# SP_Display_Line_0603.net
KiCad netlist of a schematic drawn in EAGLE
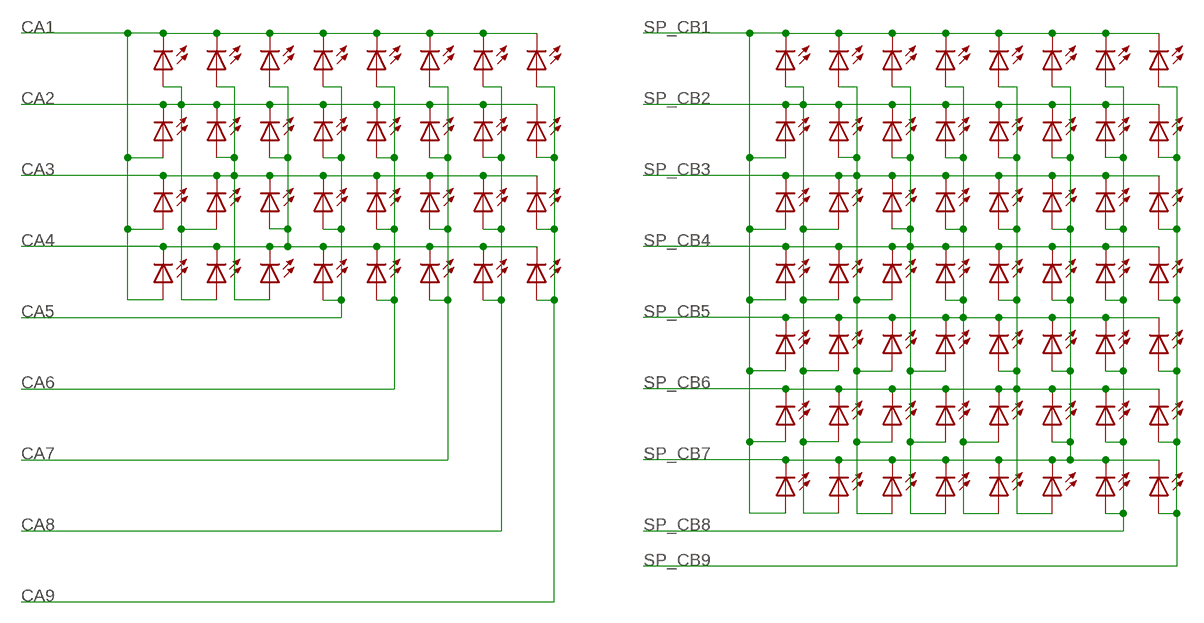
[diagram p0: schematic, sheet 1]

(export (version "E")
  (design (tool "Eeschema 10.0.6"))
  (components
    (comp (ref "LED_A1")
      (value "LEDSMT0603_1")
      (footprint "eagle-import:CHIPLED_0603")
      (libsource (lib "eagle-import") (part "LED0603_1SMT"))
    )
    (comp (ref "LED_A2")
      (value "LEDSMT0603_1")
      (footprint "eagle-import:CHIPLED_0603")
      (libsource (lib "eagle-import") (part "LED0603_1SMT"))
    )
    (comp (ref "LED_B1")
      (value "LEDSMT0603_1")
      (footprint "eagle-import:CHIPLED_0603")
      (libsource (lib "eagle-import") (part "LED0603_1SMT"))
    )
    (comp (ref "LED_B2")
      (value "LEDSMT0603_1")
      (footprint "eagle-import:CHIPLED_0603")
      (libsource (lib "eagle-import") (part "LED0603_1SMT"))
    )
    (comp (ref "LED_C1")
      (value "LEDSMT0603_1")
      (footprint "eagle-import:CHIPLED_0603")
      (libsource (lib "eagle-import") (part "LED0603_1SMT"))
    )
    (comp (ref "LED_C2")
      (value "LEDSMT0603_1")
      (footprint "eagle-import:CHIPLED_0603")
      (libsource (lib "eagle-import") (part "LED0603_1SMT"))
    )
    (comp (ref "LED_D1")
      (value "LEDSMT0603_1")
      (footprint "eagle-import:CHIPLED_0603")
      (libsource (lib "eagle-import") (part "LED0603_1SMT"))
    )
    (comp (ref "LED_D2")
      (value "LEDSMT0603_1")
      (footprint "eagle-import:CHIPLED_0603")
      (libsource (lib "eagle-import") (part "LED0603_1SMT"))
    )
    (comp (ref "LED_DA1")
      (value "LEDSMT0603_1")
      (footprint "eagle-import:CHIPLED_0603")
      (libsource (lib "eagle-import") (part "LED0603_1SMT"))
    )
    (comp (ref "LED_DA2")
      (value "LEDSMT0603_1")
      (footprint "eagle-import:CHIPLED_0603")
      (libsource (lib "eagle-import") (part "LED0603_1SMT"))
    )
    (comp (ref "LED_DA3")
      (value "LEDSMT0603_1")
      (footprint "eagle-import:CHIPLED_0603")
      (libsource (lib "eagle-import") (part "LED0603_1SMT"))
    )
    (comp (ref "LED_DA4")
      (value "LEDSMT0603_1")
      (footprint "eagle-import:CHIPLED_0603")
      (libsource (lib "eagle-import") (part "LED0603_1SMT"))
    )
    (comp (ref "LED_DA5")
      (value "LEDSMT0603_1")
      (footprint "eagle-import:CHIPLED_0603")
      (libsource (lib "eagle-import") (part "LED0603_1SMT"))
    )
    (comp (ref "LED_DA6")
      (value "LEDSMT0603_1")
      (footprint "eagle-import:CHIPLED_0603")
      (libsource (lib "eagle-import") (part "LED0603_1SMT"))
    )
    (comp (ref "LED_DA7")
      (value "LEDSMT0603_1")
      (footprint "eagle-import:CHIPLED_0603")
      (libsource (lib "eagle-import") (part "LED0603_1SMT"))
    )
    (comp (ref "LED_DB1")
      (value "LEDSMT0603_1")
      (footprint "eagle-import:CHIPLED_0603")
      (libsource (lib "eagle-import") (part "LED0603_1SMT"))
    )
    (comp (ref "LED_DB2")
      (value "LEDSMT0603_1")
      (footprint "eagle-import:CHIPLED_0603")
      (libsource (lib "eagle-import") (part "LED0603_1SMT"))
    )
    (comp (ref "LED_DB3")
      (value "LEDSMT0603_1")
      (footprint "eagle-import:CHIPLED_0603")
      (libsource (lib "eagle-import") (part "LED0603_1SMT"))
    )
    (comp (ref "LED_DB4")
      (value "LEDSMT0603_1")
      (footprint "eagle-import:CHIPLED_0603")
      (libsource (lib "eagle-import") (part "LED0603_1SMT"))
    )
    (comp (ref "LED_DB5")
      (value "LEDSMT0603_1")
      (footprint "eagle-import:CHIPLED_0603")
      (libsource (lib "eagle-import") (part "LED0603_1SMT"))
    )
    (comp (ref "LED_DB6")
      (value "LEDSMT0603_1")
      (footprint "eagle-import:CHIPLED_0603")
      (libsource (lib "eagle-import") (part "LED0603_1SMT"))
    )
    (comp (ref "LED_DB7")
      (value "LEDSMT0603_1")
      (footprint "eagle-import:CHIPLED_0603")
      (libsource (lib "eagle-import") (part "LED0603_1SMT"))
    )
    (comp (ref "LED_DC1")
      (value "LEDSMT0603_1")
      (footprint "eagle-import:CHIPLED_0603")
      (libsource (lib "eagle-import") (part "LED0603_1SMT"))
    )
    (comp (ref "LED_DC2")
      (value "LEDSMT0603_1")
      (footprint "eagle-import:CHIPLED_0603")
      (libsource (lib "eagle-import") (part "LED0603_1SMT"))
    )
    (comp (ref "LED_DC3")
      (value "LEDSMT0603_1")
      (footprint "eagle-import:CHIPLED_0603")
      (libsource (lib "eagle-import") (part "LED0603_1SMT"))
    )
    (comp (ref "LED_DC4")
      (value "LEDSMT0603_1")
      (footprint "eagle-import:CHIPLED_0603")
      (libsource (lib "eagle-import") (part "LED0603_1SMT"))
    )
    (comp (ref "LED_DC5")
      (value "LEDSMT0603_1")
      (footprint "eagle-import:CHIPLED_0603")
      (libsource (lib "eagle-import") (part "LED0603_1SMT"))
    )
    (comp (ref "LED_DC6")
      (value "LEDSMT0603_1")
      (footprint "eagle-import:CHIPLED_0603")
      (libsource (lib "eagle-import") (part "LED0603_1SMT"))
    )
    (comp (ref "LED_DC7")
      (value "LEDSMT0603_1")
      (footprint "eagle-import:CHIPLED_0603")
      (libsource (lib "eagle-import") (part "LED0603_1SMT"))
    )
    (comp (ref "LED_DD1")
      (value "LEDSMT0603_1")
      (footprint "eagle-import:CHIPLED_0603")
      (libsource (lib "eagle-import") (part "LED0603_1SMT"))
    )
    (comp (ref "LED_DD2")
      (value "LEDSMT0603_1")
      (footprint "eagle-import:CHIPLED_0603")
      (libsource (lib "eagle-import") (part "LED0603_1SMT"))
    )
    (comp (ref "LED_DD3")
      (value "LEDSMT0603_1")
      (footprint "eagle-import:CHIPLED_0603")
      (libsource (lib "eagle-import") (part "LED0603_1SMT"))
    )
    (comp (ref "LED_DD4")
      (value "LEDSMT0603_1")
      (footprint "eagle-import:CHIPLED_0603")
      (libsource (lib "eagle-import") (part "LED0603_1SMT"))
    )
    (comp (ref "LED_DD5")
      (value "LEDSMT0603_1")
      (footprint "eagle-import:CHIPLED_0603")
      (libsource (lib "eagle-import") (part "LED0603_1SMT"))
    )
    (comp (ref "LED_DD6")
      (value "LEDSMT0603_1")
      (footprint "eagle-import:CHIPLED_0603")
      (libsource (lib "eagle-import") (part "LED0603_1SMT"))
    )
    (comp (ref "LED_DD7")
      (value "LEDSMT0603_1")
      (footprint "eagle-import:CHIPLED_0603")
      (libsource (lib "eagle-import") (part "LED0603_1SMT"))
    )
    (comp (ref "LED_DE1")
      (value "LEDSMT0603_1")
      (footprint "eagle-import:CHIPLED_0603")
      (libsource (lib "eagle-import") (part "LED0603_1SMT"))
    )
    (comp (ref "LED_DE2")
      (value "LEDSMT0603_1")
      (footprint "eagle-import:CHIPLED_0603")
      (libsource (lib "eagle-import") (part "LED0603_1SMT"))
    )
    (comp (ref "LED_DE3")
      (value "LEDSMT0603_1")
      (footprint "eagle-import:CHIPLED_0603")
      (libsource (lib "eagle-import") (part "LED0603_1SMT"))
    )
    (comp (ref "LED_DE4")
      (value "LEDSMT0603_1")
      (footprint "eagle-import:CHIPLED_0603")
      (libsource (lib "eagle-import") (part "LED0603_1SMT"))
    )
    (comp (ref "LED_DE5")
      (value "LEDSMT0603_1")
      (footprint "eagle-import:CHIPLED_0603")
      (libsource (lib "eagle-import") (part "LED0603_1SMT"))
    )
    (comp (ref "LED_DE6")
      (value "LEDSMT0603_1")
      (footprint "eagle-import:CHIPLED_0603")
      (libsource (lib "eagle-import") (part "LED0603_1SMT"))
    )
    (comp (ref "LED_DE7")
      (value "LEDSMT0603_1")
      (footprint "eagle-import:CHIPLED_0603")
      (libsource (lib "eagle-import") (part "LED0603_1SMT"))
    )
    (comp (ref "LED_DF1")
      (value "LEDSMT0603_1")
      (footprint "eagle-import:CHIPLED_0603")
      (libsource (lib "eagle-import") (part "LED0603_1SMT"))
    )
    (comp (ref "LED_DF2")
      (value "LEDSMT0603_1")
      (footprint "eagle-import:CHIPLED_0603")
      (libsource (lib "eagle-import") (part "LED0603_1SMT"))
    )
    (comp (ref "LED_DF3")
      (value "LEDSMT0603_1")
      (footprint "eagle-import:CHIPLED_0603")
      (libsource (lib "eagle-import") (part "LED0603_1SMT"))
    )
    (comp (ref "LED_DF4")
      (value "LEDSMT0603_1")
      (footprint "eagle-import:CHIPLED_0603")
      (libsource (lib "eagle-import") (part "LED0603_1SMT"))
    )
    (comp (ref "LED_DF5")
      (value "LEDSMT0603_1")
      (footprint "eagle-import:CHIPLED_0603")
      (libsource (lib "eagle-import") (part "LED0603_1SMT"))
    )
    (comp (ref "LED_DF6")
      (value "LEDSMT0603_1")
      (footprint "eagle-import:CHIPLED_0603")
      (libsource (lib "eagle-import") (part "LED0603_1SMT"))
    )
    (comp (ref "LED_DF7")
      (value "LEDSMT0603_1")
      (footprint "eagle-import:CHIPLED_0603")
      (libsource (lib "eagle-import") (part "LED0603_1SMT"))
    )
    (comp (ref "LED_DG1")
      (value "LEDSMT0603_1")
      (footprint "eagle-import:CHIPLED_0603")
      (libsource (lib "eagle-import") (part "LED0603_1SMT"))
    )
    (comp (ref "LED_DG2")
      (value "LEDSMT0603_1")
      (footprint "eagle-import:CHIPLED_0603")
      (libsource (lib "eagle-import") (part "LED0603_1SMT"))
    )
    (comp (ref "LED_DG3")
      (value "LEDSMT0603_1")
      (footprint "eagle-import:CHIPLED_0603")
      (libsource (lib "eagle-import") (part "LED0603_1SMT"))
    )
    (comp (ref "LED_DG4")
      (value "LEDSMT0603_1")
      (footprint "eagle-import:CHIPLED_0603")
      (libsource (lib "eagle-import") (part "LED0603_1SMT"))
    )
    (comp (ref "LED_DG5")
      (value "LEDSMT0603_1")
      (footprint "eagle-import:CHIPLED_0603")
      (libsource (lib "eagle-import") (part "LED0603_1SMT"))
    )
    (comp (ref "LED_DG6")
      (value "LEDSMT0603_1")
      (footprint "eagle-import:CHIPLED_0603")
      (libsource (lib "eagle-import") (part "LED0603_1SMT"))
    )
    (comp (ref "LED_DG7")
      (value "LEDSMT0603_1")
      (footprint "eagle-import:CHIPLED_0603")
      (libsource (lib "eagle-import") (part "LED0603_1SMT"))
    )
    (comp (ref "LED_DP1")
      (value "LEDSMT0603_1")
      (footprint "eagle-import:CHIPLED_0603")
      (libsource (lib "eagle-import") (part "LED0603_1SMT"))
    )
    (comp (ref "LED_DP2")
      (value "LEDSMT0603_1")
      (footprint "eagle-import:CHIPLED_0603")
      (libsource (lib "eagle-import") (part "LED0603_1SMT"))
    )
    (comp (ref "LED_DP3")
      (value "LEDSMT0603_1")
      (footprint "eagle-import:CHIPLED_0603")
      (libsource (lib "eagle-import") (part "LED0603_1SMT"))
    )
    (comp (ref "LED_DP4")
      (value "LEDSMT0603_1")
      (footprint "eagle-import:CHIPLED_0603")
      (libsource (lib "eagle-import") (part "LED0603_1SMT"))
    )
    (comp (ref "LED_DP5")
      (value "LEDSMT0603_1")
      (footprint "eagle-import:CHIPLED_0603")
      (libsource (lib "eagle-import") (part "LED0603_1SMT"))
    )
    (comp (ref "LED_DP6")
      (value "LEDSMT0603_1")
      (footprint "eagle-import:CHIPLED_0603")
      (libsource (lib "eagle-import") (part "LED0603_1SMT"))
    )
    (comp (ref "LED_DP7")
      (value "LEDSMT0603_1")
      (footprint "eagle-import:CHIPLED_0603")
      (libsource (lib "eagle-import") (part "LED0603_1SMT"))
    )
    (comp (ref "LED_E1")
      (value "LEDSMT0603_1")
      (footprint "eagle-import:CHIPLED_0603")
      (libsource (lib "eagle-import") (part "LED0603_1SMT"))
    )
    (comp (ref "LED_E2")
      (value "LEDSMT0603_1")
      (footprint "eagle-import:CHIPLED_0603")
      (libsource (lib "eagle-import") (part "LED0603_1SMT"))
    )
    (comp (ref "LED_F1")
      (value "LEDSMT0603_1")
      (footprint "eagle-import:CHIPLED_0603")
      (libsource (lib "eagle-import") (part "LED0603_1SMT"))
    )
    (comp (ref "LED_F2")
      (value "LEDSMT0603_1")
      (footprint "eagle-import:CHIPLED_0603")
      (libsource (lib "eagle-import") (part "LED0603_1SMT"))
    )
    (comp (ref "LED_G1")
      (value "LEDSMT0603_1")
      (footprint "eagle-import:CHIPLED_0603")
      (libsource (lib "eagle-import") (part "LED0603_1SMT"))
    )
    (comp (ref "LED_G2")
      (value "LEDSMT0603_1")
      (footprint "eagle-import:CHIPLED_0603")
      (libsource (lib "eagle-import") (part "LED0603_1SMT"))
    )
    (comp (ref "LED_H1")
      (value "LEDSMT0603_1")
      (footprint "eagle-import:CHIPLED_0603")
      (libsource (lib "eagle-import") (part "LED0603_1SMT"))
    )
    (comp (ref "LED_H2")
      (value "LEDSMT0603_1")
      (footprint "eagle-import:CHIPLED_0603")
      (libsource (lib "eagle-import") (part "LED0603_1SMT"))
    )
    (comp (ref "LED_K1")
      (value "LEDSMT0603_1")
      (footprint "eagle-import:CHIPLED_0603")
      (libsource (lib "eagle-import") (part "LED0603_1SMT"))
    )
    (comp (ref "LED_K2")
      (value "LEDSMT0603_1")
      (footprint "eagle-import:CHIPLED_0603")
      (libsource (lib "eagle-import") (part "LED0603_1SMT"))
    )
    (comp (ref "LED_M1")
      (value "LEDSMT0603_1")
      (footprint "eagle-import:CHIPLED_0603")
      (libsource (lib "eagle-import") (part "LED0603_1SMT"))
    )
    (comp (ref "LED_M2")
      (value "LEDSMT0603_1")
      (footprint "eagle-import:CHIPLED_0603")
      (libsource (lib "eagle-import") (part "LED0603_1SMT"))
    )
    (comp (ref "LED_N1")
      (value "LEDSMT0603_1")
      (footprint "eagle-import:CHIPLED_0603")
      (libsource (lib "eagle-import") (part "LED0603_1SMT"))
    )
    (comp (ref "LED_N2")
      (value "LEDSMT0603_1")
      (footprint "eagle-import:CHIPLED_0603")
      (libsource (lib "eagle-import") (part "LED0603_1SMT"))
    )
    (comp (ref "LED_P1")
      (value "LEDSMT0603_1")
      (footprint "eagle-import:CHIPLED_0603")
      (libsource (lib "eagle-import") (part "LED0603_1SMT"))
    )
    (comp (ref "LED_P2")
      (value "LEDSMT0603_1")
      (footprint "eagle-import:CHIPLED_0603")
      (libsource (lib "eagle-import") (part "LED0603_1SMT"))
    )
    (comp (ref "LED_R1")
      (value "LEDSMT0603_1")
      (footprint "eagle-import:CHIPLED_0603")
      (libsource (lib "eagle-import") (part "LED0603_1SMT"))
    )
    (comp (ref "LED_R2")
      (value "LEDSMT0603_1")
      (footprint "eagle-import:CHIPLED_0603")
      (libsource (lib "eagle-import") (part "LED0603_1SMT"))
    )
    (comp (ref "LED_S1")
      (value "LEDSMT0603_1")
      (footprint "eagle-import:CHIPLED_0603")
      (libsource (lib "eagle-import") (part "LED0603_1SMT"))
    )
    (comp (ref "LED_S2")
      (value "LEDSMT0603_1")
      (footprint "eagle-import:CHIPLED_0603")
      (libsource (lib "eagle-import") (part "LED0603_1SMT"))
    )
    (comp (ref "LED_T1")
      (value "LEDSMT0603_1")
      (footprint "eagle-import:CHIPLED_0603")
      (libsource (lib "eagle-import") (part "LED0603_1SMT"))
    )
    (comp (ref "LED_T2")
      (value "LEDSMT0603_1")
      (footprint "eagle-import:CHIPLED_0603")
      (libsource (lib "eagle-import") (part "LED0603_1SMT"))
    )
    (comp (ref "LED_U1")
      (value "LEDSMT0603_1")
      (footprint "eagle-import:CHIPLED_0603")
      (libsource (lib "eagle-import") (part "LED0603_1SMT"))
    )
    (comp (ref "LED_U2")
      (value "LEDSMT0603_1")
      (footprint "eagle-import:CHIPLED_0603")
      (libsource (lib "eagle-import") (part "LED0603_1SMT"))
    )
  )
  (nets
    (net (code "1") (name "/CA1") (class "Default")
      (node (ref "LED_A1") (pin "C") (pinfunction "C_C") (pintype "passive"))
      (node (ref "LED_A2") (pin "A") (pinfunction "A_A") (pintype "passive"))
      (node (ref "LED_B1") (pin "C") (pinfunction "C_C") (pintype "passive"))
      (node (ref "LED_C1") (pin "C") (pinfunction "C_C") (pintype "passive"))
      (node (ref "LED_D1") (pin "C") (pinfunction "C_C") (pintype "passive"))
      (node (ref "LED_E1") (pin "C") (pinfunction "C_C") (pintype "passive"))
      (node (ref "LED_F1") (pin "C") (pinfunction "C_C") (pintype "passive"))
      (node (ref "LED_G1") (pin "C") (pinfunction "C_C") (pintype "passive"))
      (node (ref "LED_H1") (pin "C") (pinfunction "C_C") (pintype "passive"))
      (node (ref "LED_K1") (pin "A") (pinfunction "A_A") (pintype "passive"))
      (node (ref "LED_K2") (pin "A") (pinfunction "A_A") (pintype "passive"))
    )
    (net (code "2") (name "/CA2") (class "Default")
      (node (ref "LED_A1") (pin "A") (pinfunction "A_A") (pintype "passive"))
      (node (ref "LED_B2") (pin "A") (pinfunction "A_A") (pintype "passive"))
      (node (ref "LED_K1") (pin "C") (pinfunction "C_C") (pintype "passive"))
      (node (ref "LED_M1") (pin "C") (pinfunction "C_C") (pintype "passive"))
      (node (ref "LED_M2") (pin "A") (pinfunction "A_A") (pintype "passive"))
      (node (ref "LED_N1") (pin "C") (pinfunction "C_C") (pintype "passive"))
      (node (ref "LED_P1") (pin "C") (pinfunction "C_C") (pintype "passive"))
      (node (ref "LED_R1") (pin "C") (pinfunction "C_C") (pintype "passive"))
      (node (ref "LED_S1") (pin "C") (pinfunction "C_C") (pintype "passive"))
      (node (ref "LED_T1") (pin "C") (pinfunction "C_C") (pintype "passive"))
      (node (ref "LED_U1") (pin "C") (pinfunction "C_C") (pintype "passive"))
    )
    (net (code "3") (name "/CA3") (class "Default")
      (node (ref "LED_A2") (pin "C") (pinfunction "C_C") (pintype "passive"))
      (node (ref "LED_B1") (pin "A") (pinfunction "A_A") (pintype "passive"))
      (node (ref "LED_B2") (pin "C") (pinfunction "C_C") (pintype "passive"))
      (node (ref "LED_C2") (pin "C") (pinfunction "C_C") (pintype "passive"))
      (node (ref "LED_D2") (pin "C") (pinfunction "C_C") (pintype "passive"))
      (node (ref "LED_E2") (pin "C") (pinfunction "C_C") (pintype "passive"))
      (node (ref "LED_F2") (pin "C") (pinfunction "C_C") (pintype "passive"))
      (node (ref "LED_G2") (pin "C") (pinfunction "C_C") (pintype "passive"))
      (node (ref "LED_H2") (pin "C") (pinfunction "C_C") (pintype "passive"))
      (node (ref "LED_M1") (pin "A") (pinfunction "A_A") (pintype "passive"))
      (node (ref "LED_N2") (pin "A") (pinfunction "A_A") (pintype "passive"))
    )
    (net (code "4") (name "/CA4") (class "Default")
      (node (ref "LED_C1") (pin "A") (pinfunction "A_A") (pintype "passive"))
      (node (ref "LED_C2") (pin "A") (pinfunction "A_A") (pintype "passive"))
      (node (ref "LED_K2") (pin "C") (pinfunction "C_C") (pintype "passive"))
      (node (ref "LED_M2") (pin "C") (pinfunction "C_C") (pintype "passive"))
      (node (ref "LED_N1") (pin "A") (pinfunction "A_A") (pintype "passive"))
      (node (ref "LED_N2") (pin "C") (pinfunction "C_C") (pintype "passive"))
      (node (ref "LED_P2") (pin "C") (pinfunction "C_C") (pintype "passive"))
      (node (ref "LED_R2") (pin "C") (pinfunction "C_C") (pintype "passive"))
      (node (ref "LED_S2") (pin "C") (pinfunction "C_C") (pintype "passive"))
      (node (ref "LED_T2") (pin "C") (pinfunction "C_C") (pintype "passive"))
      (node (ref "LED_U2") (pin "C") (pinfunction "C_C") (pintype "passive"))
    )
    (net (code "5") (name "/CA5") (class "Default")
      (node (ref "LED_D1") (pin "A") (pinfunction "A_A") (pintype "passive"))
      (node (ref "LED_D2") (pin "A") (pinfunction "A_A") (pintype "passive"))
      (node (ref "LED_P1") (pin "A") (pinfunction "A_A") (pintype "passive"))
      (node (ref "LED_P2") (pin "A") (pinfunction "A_A") (pintype "passive"))
    )
    (net (code "6") (name "/CA6") (class "Default")
      (node (ref "LED_E1") (pin "A") (pinfunction "A_A") (pintype "passive"))
      (node (ref "LED_E2") (pin "A") (pinfunction "A_A") (pintype "passive"))
      (node (ref "LED_R1") (pin "A") (pinfunction "A_A") (pintype "passive"))
      (node (ref "LED_R2") (pin "A") (pinfunction "A_A") (pintype "passive"))
    )
    (net (code "7") (name "/CA7") (class "Default")
      (node (ref "LED_F1") (pin "A") (pinfunction "A_A") (pintype "passive"))
      (node (ref "LED_F2") (pin "A") (pinfunction "A_A") (pintype "passive"))
      (node (ref "LED_S1") (pin "A") (pinfunction "A_A") (pintype "passive"))
      (node (ref "LED_S2") (pin "A") (pinfunction "A_A") (pintype "passive"))
    )
    (net (code "8") (name "/CA8") (class "Default")
      (node (ref "LED_G1") (pin "A") (pinfunction "A_A") (pintype "passive"))
      (node (ref "LED_G2") (pin "A") (pinfunction "A_A") (pintype "passive"))
      (node (ref "LED_T1") (pin "A") (pinfunction "A_A") (pintype "passive"))
      (node (ref "LED_T2") (pin "A") (pinfunction "A_A") (pintype "passive"))
    )
    (net (code "9") (name "/CA9") (class "Default")
      (node (ref "LED_H1") (pin "A") (pinfunction "A_A") (pintype "passive"))
      (node (ref "LED_H2") (pin "A") (pinfunction "A_A") (pintype "passive"))
      (node (ref "LED_U1") (pin "A") (pinfunction "A_A") (pintype "passive"))
      (node (ref "LED_U2") (pin "A") (pinfunction "A_A") (pintype "passive"))
    )
    (net (code "10") (name "/SP_CB1") (class "Default")
      (node (ref "LED_DA1") (pin "C") (pinfunction "C_C") (pintype "passive"))
      (node (ref "LED_DA2") (pin "A") (pinfunction "A_A") (pintype "passive"))
      (node (ref "LED_DA3") (pin "A") (pinfunction "A_A") (pintype "passive"))
      (node (ref "LED_DA4") (pin "A") (pinfunction "A_A") (pintype "passive"))
      (node (ref "LED_DA5") (pin "A") (pinfunction "A_A") (pintype "passive"))
      (node (ref "LED_DA6") (pin "A") (pinfunction "A_A") (pintype "passive"))
      (node (ref "LED_DA7") (pin "A") (pinfunction "A_A") (pintype "passive"))
      (node (ref "LED_DB1") (pin "C") (pinfunction "C_C") (pintype "passive"))
      (node (ref "LED_DC1") (pin "C") (pinfunction "C_C") (pintype "passive"))
      (node (ref "LED_DD1") (pin "C") (pinfunction "C_C") (pintype "passive"))
      (node (ref "LED_DE1") (pin "C") (pinfunction "C_C") (pintype "passive"))
      (node (ref "LED_DF1") (pin "C") (pinfunction "C_C") (pintype "passive"))
      (node (ref "LED_DG1") (pin "C") (pinfunction "C_C") (pintype "passive"))
      (node (ref "LED_DP1") (pin "C") (pinfunction "C_C") (pintype "passive"))
    )
    (net (code "11") (name "/SP_CB2") (class "Default")
      (node (ref "LED_DA1") (pin "A") (pinfunction "A_A") (pintype "passive"))
      (node (ref "LED_DA2") (pin "C") (pinfunction "C_C") (pintype "passive"))
      (node (ref "LED_DB2") (pin "C") (pinfunction "C_C") (pintype "passive"))
      (node (ref "LED_DB3") (pin "A") (pinfunction "A_A") (pintype "passive"))
      (node (ref "LED_DB4") (pin "A") (pinfunction "A_A") (pintype "passive"))
      (node (ref "LED_DB5") (pin "A") (pinfunction "A_A") (pintype "passive"))
      (node (ref "LED_DB6") (pin "A") (pinfunction "A_A") (pintype "passive"))
      (node (ref "LED_DB7") (pin "A") (pinfunction "A_A") (pintype "passive"))
      (node (ref "LED_DC2") (pin "C") (pinfunction "C_C") (pintype "passive"))
      (node (ref "LED_DD2") (pin "C") (pinfunction "C_C") (pintype "passive"))
      (node (ref "LED_DE2") (pin "C") (pinfunction "C_C") (pintype "passive"))
      (node (ref "LED_DF2") (pin "C") (pinfunction "C_C") (pintype "passive"))
      (node (ref "LED_DG2") (pin "C") (pinfunction "C_C") (pintype "passive"))
      (node (ref "LED_DP2") (pin "C") (pinfunction "C_C") (pintype "passive"))
    )
    (net (code "12") (name "/SP_CB3") (class "Default")
      (node (ref "LED_DA3") (pin "C") (pinfunction "C_C") (pintype "passive"))
      (node (ref "LED_DB1") (pin "A") (pinfunction "A_A") (pintype "passive"))
      (node (ref "LED_DB2") (pin "A") (pinfunction "A_A") (pintype "passive"))
      (node (ref "LED_DB3") (pin "C") (pinfunction "C_C") (pintype "passive"))
      (node (ref "LED_DC3") (pin "C") (pinfunction "C_C") (pintype "passive"))
      (node (ref "LED_DC4") (pin "A") (pinfunction "A_A") (pintype "passive"))
      (node (ref "LED_DC5") (pin "A") (pinfunction "A_A") (pintype "passive"))
      (node (ref "LED_DC6") (pin "A") (pinfunction "A_A") (pintype "passive"))
      (node (ref "LED_DC7") (pin "A") (pinfunction "A_A") (pintype "passive"))
      (node (ref "LED_DD3") (pin "C") (pinfunction "C_C") (pintype "passive"))
      (node (ref "LED_DE3") (pin "C") (pinfunction "C_C") (pintype "passive"))
      (node (ref "LED_DF3") (pin "C") (pinfunction "C_C") (pintype "passive"))
      (node (ref "LED_DG3") (pin "C") (pinfunction "C_C") (pintype "passive"))
      (node (ref "LED_DP3") (pin "C") (pinfunction "C_C") (pintype "passive"))
    )
    (net (code "13") (name "/SP_CB4") (class "Default")
      (node (ref "LED_DA4") (pin "C") (pinfunction "C_C") (pintype "passive"))
      (node (ref "LED_DB4") (pin "C") (pinfunction "C_C") (pintype "passive"))
      (node (ref "LED_DC1") (pin "A") (pinfunction "A_A") (pintype "passive"))
      (node (ref "LED_DC2") (pin "A") (pinfunction "A_A") (pintype "passive"))
      (node (ref "LED_DC3") (pin "A") (pinfunction "A_A") (pintype "passive"))
      (node (ref "LED_DC4") (pin "C") (pinfunction "C_C") (pintype "passive"))
      (node (ref "LED_DD4") (pin "C") (pinfunction "C_C") (pintype "passive"))
      (node (ref "LED_DD5") (pin "A") (pinfunction "A_A") (pintype "passive"))
      (node (ref "LED_DD6") (pin "A") (pinfunction "A_A") (pintype "passive"))
      (node (ref "LED_DD7") (pin "A") (pinfunction "A_A") (pintype "passive"))
      (node (ref "LED_DE4") (pin "C") (pinfunction "C_C") (pintype "passive"))
      (node (ref "LED_DF4") (pin "C") (pinfunction "C_C") (pintype "passive"))
      (node (ref "LED_DG4") (pin "C") (pinfunction "C_C") (pintype "passive"))
      (node (ref "LED_DP4") (pin "C") (pinfunction "C_C") (pintype "passive"))
    )
    (net (code "14") (name "/SP_CB5") (class "Default")
      (node (ref "LED_DA5") (pin "C") (pinfunction "C_C") (pintype "passive"))
      (node (ref "LED_DB5") (pin "C") (pinfunction "C_C") (pintype "passive"))
      (node (ref "LED_DC5") (pin "C") (pinfunction "C_C") (pintype "passive"))
      (node (ref "LED_DD1") (pin "A") (pinfunction "A_A") (pintype "passive"))
      (node (ref "LED_DD2") (pin "A") (pinfunction "A_A") (pintype "passive"))
      (node (ref "LED_DD3") (pin "A") (pinfunction "A_A") (pintype "passive"))
      (node (ref "LED_DD4") (pin "A") (pinfunction "A_A") (pintype "passive"))
      (node (ref "LED_DD5") (pin "C") (pinfunction "C_C") (pintype "passive"))
      (node (ref "LED_DE5") (pin "C") (pinfunction "C_C") (pintype "passive"))
      (node (ref "LED_DE6") (pin "A") (pinfunction "A_A") (pintype "passive"))
      (node (ref "LED_DE7") (pin "A") (pinfunction "A_A") (pintype "passive"))
      (node (ref "LED_DF5") (pin "C") (pinfunction "C_C") (pintype "passive"))
      (node (ref "LED_DG5") (pin "C") (pinfunction "C_C") (pintype "passive"))
      (node (ref "LED_DP5") (pin "C") (pinfunction "C_C") (pintype "passive"))
    )
    (net (code "15") (name "/SP_CB6") (class "Default")
      (node (ref "LED_DA6") (pin "C") (pinfunction "C_C") (pintype "passive"))
      (node (ref "LED_DB6") (pin "C") (pinfunction "C_C") (pintype "passive"))
      (node (ref "LED_DC6") (pin "C") (pinfunction "C_C") (pintype "passive"))
      (node (ref "LED_DD6") (pin "C") (pinfunction "C_C") (pintype "passive"))
      (node (ref "LED_DE1") (pin "A") (pinfunction "A_A") (pintype "passive"))
      (node (ref "LED_DE2") (pin "A") (pinfunction "A_A") (pintype "passive"))
      (node (ref "LED_DE3") (pin "A") (pinfunction "A_A") (pintype "passive"))
      (node (ref "LED_DE4") (pin "A") (pinfunction "A_A") (pintype "passive"))
      (node (ref "LED_DE5") (pin "A") (pinfunction "A_A") (pintype "passive"))
      (node (ref "LED_DE6") (pin "C") (pinfunction "C_C") (pintype "passive"))
      (node (ref "LED_DF6") (pin "C") (pinfunction "C_C") (pintype "passive"))
      (node (ref "LED_DF7") (pin "A") (pinfunction "A_A") (pintype "passive"))
      (node (ref "LED_DG6") (pin "C") (pinfunction "C_C") (pintype "passive"))
      (node (ref "LED_DP6") (pin "C") (pinfunction "C_C") (pintype "passive"))
    )
    (net (code "16") (name "/SP_CB7") (class "Default")
      (node (ref "LED_DA7") (pin "C") (pinfunction "C_C") (pintype "passive"))
      (node (ref "LED_DB7") (pin "C") (pinfunction "C_C") (pintype "passive"))
      (node (ref "LED_DC7") (pin "C") (pinfunction "C_C") (pintype "passive"))
      (node (ref "LED_DD7") (pin "C") (pinfunction "C_C") (pintype "passive"))
      (node (ref "LED_DE7") (pin "C") (pinfunction "C_C") (pintype "passive"))
      (node (ref "LED_DF1") (pin "A") (pinfunction "A_A") (pintype "passive"))
      (node (ref "LED_DF2") (pin "A") (pinfunction "A_A") (pintype "passive"))
      (node (ref "LED_DF3") (pin "A") (pinfunction "A_A") (pintype "passive"))
      (node (ref "LED_DF4") (pin "A") (pinfunction "A_A") (pintype "passive"))
      (node (ref "LED_DF5") (pin "A") (pinfunction "A_A") (pintype "passive"))
      (node (ref "LED_DF6") (pin "A") (pinfunction "A_A") (pintype "passive"))
      (node (ref "LED_DF7") (pin "C") (pinfunction "C_C") (pintype "passive"))
      (node (ref "LED_DG7") (pin "C") (pinfunction "C_C") (pintype "passive"))
      (node (ref "LED_DP7") (pin "C") (pinfunction "C_C") (pintype "passive"))
    )
    (net (code "17") (name "/SP_CB8") (class "Default")
      (node (ref "LED_DG1") (pin "A") (pinfunction "A_A") (pintype "passive"))
      (node (ref "LED_DG2") (pin "A") (pinfunction "A_A") (pintype "passive"))
      (node (ref "LED_DG3") (pin "A") (pinfunction "A_A") (pintype "passive"))
      (node (ref "LED_DG4") (pin "A") (pinfunction "A_A") (pintype "passive"))
      (node (ref "LED_DG5") (pin "A") (pinfunction "A_A") (pintype "passive"))
      (node (ref "LED_DG6") (pin "A") (pinfunction "A_A") (pintype "passive"))
      (node (ref "LED_DG7") (pin "A") (pinfunction "A_A") (pintype "passive"))
    )
    (net (code "18") (name "/SP_CB9") (class "Default")
      (node (ref "LED_DP1") (pin "A") (pinfunction "A_A") (pintype "passive"))
      (node (ref "LED_DP2") (pin "A") (pinfunction "A_A") (pintype "passive"))
      (node (ref "LED_DP3") (pin "A") (pinfunction "A_A") (pintype "passive"))
      (node (ref "LED_DP4") (pin "A") (pinfunction "A_A") (pintype "passive"))
      (node (ref "LED_DP5") (pin "A") (pinfunction "A_A") (pintype "passive"))
      (node (ref "LED_DP6") (pin "A") (pinfunction "A_A") (pintype "passive"))
      (node (ref "LED_DP7") (pin "A") (pinfunction "A_A") (pintype "passive"))
    )
  )
)
